# Zigbee.net
KiCad netlist of a schematic drawn in Altium Designer
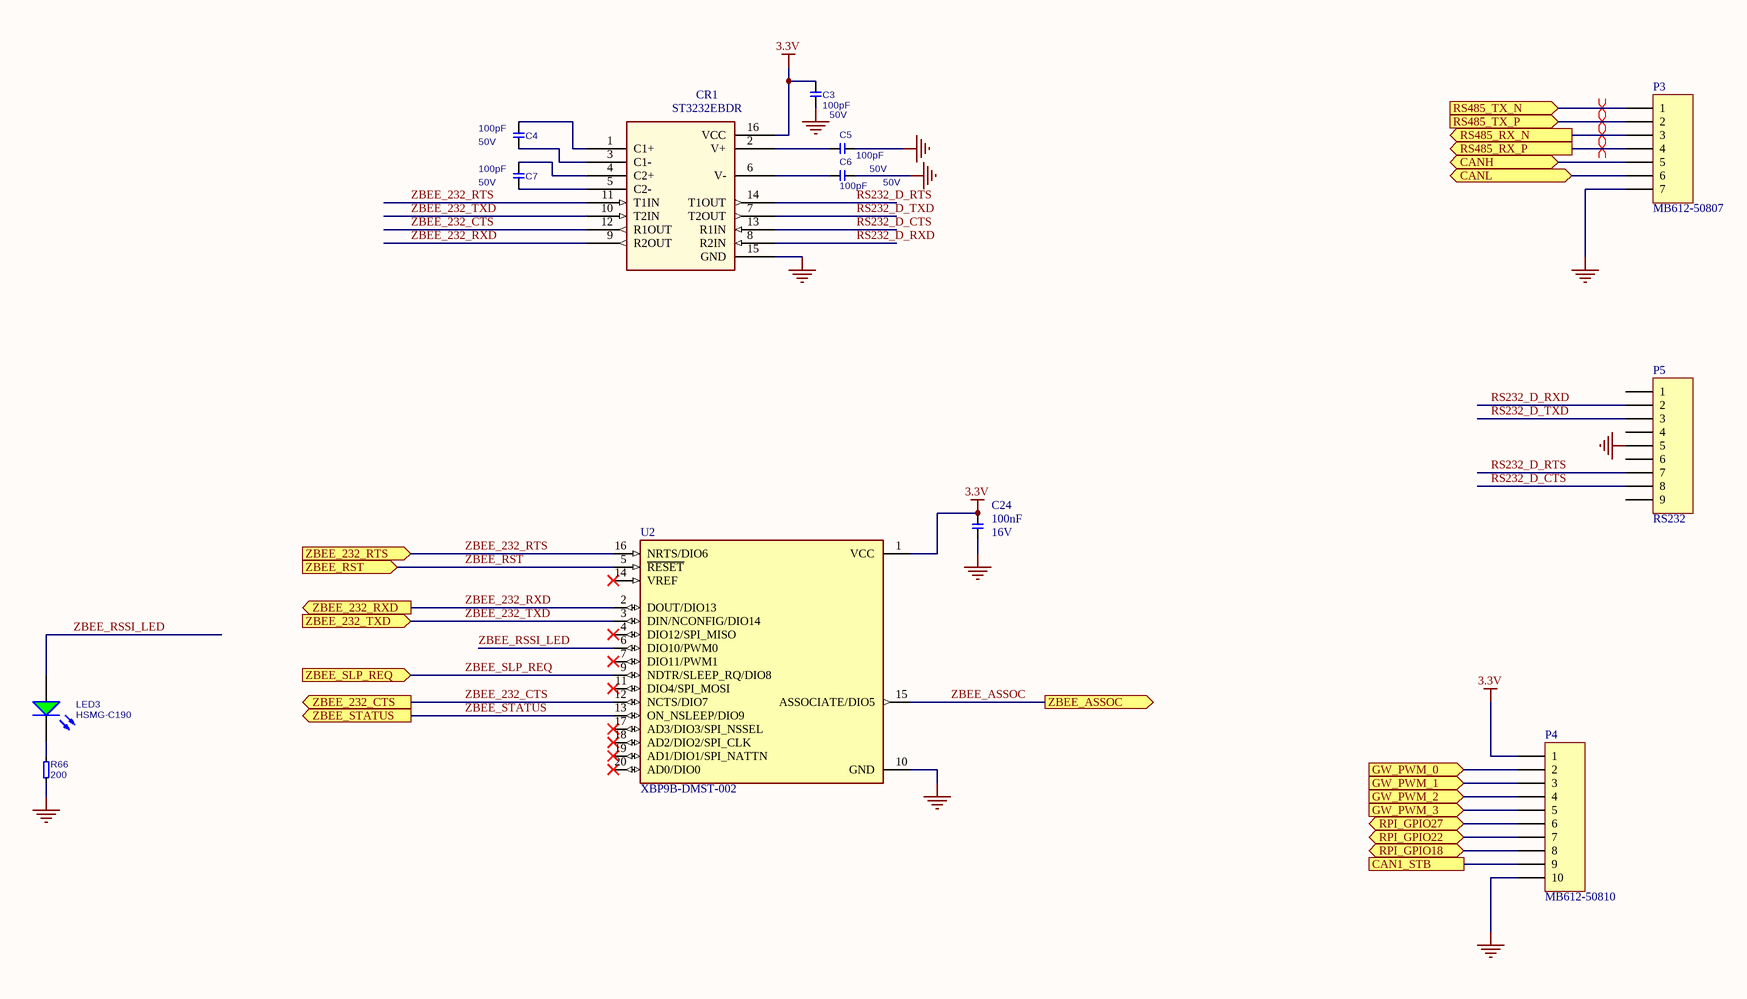
[diagram p0: Zigbee.SchDoc]

(export (version "E")
  (design (tool "Eeschema 10.0.6"))
  (components
    (comp (ref "C3")
      (value "100pF")
      (footprint "CAPC1005X60N")
      (description "Capacitor Ceramic X7R 100pF 50V 10% 0402")
      (fields (field (name "TOLERANCE") "10%") (field (name "RATING") "50V"))
      (libsource (lib "Iris") (part "C-X7R-100pF-50V-10%-0402"))
    )
    (comp (ref "C4")
      (value "100pF")
      (footprint "CAPC1005X60N")
      (description "Capacitor Ceramic X7R 100pF 50V 10% 0402")
      (fields (field (name "TOLERANCE") "10%") (field (name "RATING") "50V"))
      (libsource (lib "Iris") (part "C-X7R-100pF-50V-10%-0402"))
    )
    (comp (ref "C5")
      (value "100pF")
      (footprint "CAPC1005X60N")
      (description "Capacitor Ceramic X7R 100pF 50V 10% 0402")
      (fields (field (name "TOLERANCE") "10%") (field (name "RATING") "50V"))
      (libsource (lib "Iris") (part "C-X7R-100pF-50V-10%-0402"))
    )
    (comp (ref "C6")
      (value "100pF")
      (footprint "CAPC1005X60N")
      (description "Capacitor Ceramic X7R 100pF 50V 10% 0402")
      (fields (field (name "TOLERANCE") "10%") (field (name "RATING") "50V"))
      (libsource (lib "Iris") (part "C-X7R-100pF-50V-10%-0402"))
    )
    (comp (ref "C7")
      (value "100pF")
      (footprint "CAPC1005X60N")
      (description "Capacitor Ceramic X7R 100pF 50V 10% 0402")
      (fields (field (name "TOLERANCE") "10%") (field (name "RATING") "50V"))
      (libsource (lib "Iris") (part "C-X7R-100pF-50V-10%-0402"))
    )
    (comp (ref "C24")
      (value "100nF")
      (footprint "T_CAPC0603X33N")
      (description "Capacitor Ceramic X7R 100nF 16V 10% 0603")
      (fields (field (name "TOLERANCE") "10%") (field (name "RATING") "16V"))
      (libsource (lib "Iris") (part "C-X7R-100nF-16V-10%-0603"))
    )
    (comp (ref "CR1")
      (value "ST3232EBDR")
      (footprint "SO-16_STM")
      (libsource (lib "Schlib1") (part "ST3232EBDR"))
    )
    (comp (ref "LED3")
      (value "LED")
      (footprint "LEDC1608X80N")
      (description "Surface mount LED green 20mA")
      (fields (field (name "MANUFACTURER PART NO.") "HSMG-C190"))
      (libsource (lib "Iris") (part "LED-Avago-HSMG-C190"))
    )
    (comp (ref "P3")
      (value "MB612-50807")
      (footprint "MB612-50807")
      (description "Header, 7-Pin")
      (fields (field (name "PUBLISHER") "Altium Limited"))
      (libsource (lib "Miscellaneous Connectors") (part "Header 7"))
    )
    (comp (ref "P4")
      (value "MB612-50810")
      (footprint "1729186 5.08 - 10pos")
      (description "Header, 10-Pin")
      (fields (field (name "PUBLISHER") "Altium Limited"))
      (libsource (lib "Miscellaneous Connectors") (part "Header 10"))
    )
    (comp (ref "P5")
      (value "RS232")
      (footprint "2301843-1")
      (description "2301843-1")
      (fields (field (name "PUBLISHER") "Altium Limited"))
      (libsource (lib "Miscellaneous Connectors") (part "Header 9"))
    )
    (comp (ref "R66")
      (value "200")
      (footprint "RESC1005X40N")
      (description "Resistor 1 Kohm 63mW 5% 0402")
      (fields (field (name "TOLERANCE") "5%"))
      (libsource (lib "Iris") (part "R-1KR-63mW-5%-0402"))
    )
    (comp (ref "U2")
      (value "XBP9B-DMST-002")
      (footprint "DIP2200W51P200L3294H279Q20P")
      (description "General ISM < 1GHz Transceiver Module 900MHz Antenna Not Included, RP-SMA Through Hole")
      (fields (field (name "MF") "Digi International"))
      (libsource (lib "Schlib1") (part "XBP9B-DMST-002"))
    )
  )
  (nets
    (net (code "1") (name "/CAN1_STB") (class "Default")
      (node (ref "P4") (pin "9") (pinfunction "9_9") (pintype "passive"))
    )
    (net (code "2") (name "/CANH") (class "Default")
      (node (ref "P3") (pin "5") (pinfunction "5_5") (pintype "passive"))
    )
    (net (code "3") (name "/CANL") (class "Default")
      (node (ref "P3") (pin "6") (pinfunction "6_6") (pintype "passive"))
    )
    (net (code "4") (name "/GW_PWM_0") (class "Default")
      (node (ref "P4") (pin "2") (pinfunction "2_2") (pintype "passive"))
    )
    (net (code "5") (name "/GW_PWM_1") (class "Default")
      (node (ref "P4") (pin "3") (pinfunction "3_3") (pintype "passive"))
    )
    (net (code "6") (name "/GW_PWM_2") (class "Default")
      (node (ref "P4") (pin "4") (pinfunction "4_4") (pintype "passive"))
    )
    (net (code "7") (name "/GW_PWM_3") (class "Default")
      (node (ref "P4") (pin "5") (pinfunction "5_5") (pintype "passive"))
    )
    (net (code "8") (name "/RPI_GPIO18") (class "Default")
      (node (ref "P4") (pin "8") (pinfunction "8_8") (pintype "passive"))
    )
    (net (code "9") (name "/RPI_GPIO22") (class "Default")
      (node (ref "P4") (pin "7") (pinfunction "7_7") (pintype "passive"))
    )
    (net (code "10") (name "/RPI_GPIO27") (class "Default")
      (node (ref "P4") (pin "6") (pinfunction "6_6") (pintype "passive"))
    )
    (net (code "11") (name "/RS232_D_CTS") (class "Default")
      (node (ref "CR1") (pin "13") (pinfunction "R1IN_13") (pintype "input"))
      (node (ref "P5") (pin "8") (pinfunction "8_8") (pintype "passive"))
    )
    (net (code "12") (name "/RS232_D_RTS") (class "Default")
      (node (ref "CR1") (pin "14") (pinfunction "T1OUT_14") (pintype "output"))
      (node (ref "P5") (pin "7") (pinfunction "7_7") (pintype "passive"))
    )
    (net (code "13") (name "/RS232_D_RXD") (class "Default")
      (node (ref "CR1") (pin "8") (pinfunction "R2IN_8") (pintype "input"))
      (node (ref "P5") (pin "2") (pinfunction "2_2") (pintype "passive"))
    )
    (net (code "14") (name "/RS232_D_TXD") (class "Default")
      (node (ref "CR1") (pin "7") (pinfunction "T2OUT_7") (pintype "output"))
      (node (ref "P5") (pin "3") (pinfunction "3_3") (pintype "passive"))
    )
    (net (code "15") (name "/RS485_RX_N") (class "Default")
      (node (ref "P3") (pin "3") (pinfunction "3_3") (pintype "passive"))
    )
    (net (code "16") (name "/RS485_RX_P") (class "Default")
      (node (ref "P3") (pin "4") (pinfunction "4_4") (pintype "passive"))
    )
    (net (code "17") (name "/RS485_TX_N") (class "Default")
      (node (ref "P3") (pin "1") (pinfunction "1_1") (pintype "passive"))
    )
    (net (code "18") (name "/RS485_TX_P") (class "Default")
      (node (ref "P3") (pin "2") (pinfunction "2_2") (pintype "passive"))
    )
    (net (code "19") (name "/ZBEE_232_CTS") (class "Default")
      (node (ref "CR1") (pin "12") (pinfunction "R1OUT_12") (pintype "output"))
      (node (ref "U2") (pin "12") (pinfunction "NCTS/DIO7_12") (pintype "bidirectional"))
    )
    (net (code "20") (name "/ZBEE_232_RTS") (class "Default")
      (node (ref "CR1") (pin "11") (pinfunction "T1IN_11") (pintype "input"))
      (node (ref "U2") (pin "16") (pinfunction "NRTS/DIO6_16") (pintype "input"))
    )
    (net (code "21") (name "/ZBEE_232_RXD") (class "Default")
      (node (ref "CR1") (pin "9") (pinfunction "R2OUT_9") (pintype "output"))
      (node (ref "U2") (pin "2") (pinfunction "DOUT/DIO13_2") (pintype "bidirectional"))
    )
    (net (code "22") (name "/ZBEE_232_TXD") (class "Default")
      (node (ref "CR1") (pin "10") (pinfunction "T2IN_10") (pintype "input"))
      (node (ref "U2") (pin "3") (pinfunction "DIN/NCONFIG/DIO14_3") (pintype "bidirectional"))
    )
    (net (code "23") (name "/ZBEE_ASSOC") (class "Default")
      (node (ref "U2") (pin "15") (pinfunction "ASSOCIATE/DIO5_15") (pintype "output"))
    )
    (net (code "24") (name "/ZBEE_RSSI_LED") (class "Default")
      (node (ref "LED3") (pin "2") (pinfunction "A_2") (pintype "passive"))
      (node (ref "U2") (pin "6") (pinfunction "DIO10/PWM0_6") (pintype "bidirectional"))
    )
    (net (code "25") (name "/ZBEE_RST") (class "Default")
      (node (ref "U2") (pin "5") (pinfunction "~{RESET}_5") (pintype "input"))
    )
    (net (code "26") (name "/ZBEE_SLP_REQ") (class "Default")
      (node (ref "U2") (pin "9") (pinfunction "NDTR/SLEEP_RQ/DIO8_9") (pintype "bidirectional"))
    )
    (net (code "27") (name "/ZBEE_STATUS") (class "Default")
      (node (ref "U2") (pin "13") (pinfunction "ON_NSLEEP/DIO9_13") (pintype "bidirectional"))
    )
    (net (code "28") (name "3.3V") (class "Default")
      (node (ref "C24") (pin "2") (pinfunction "2_2") (pintype "passive"))
      (node (ref "C3") (pin "1") (pinfunction "1_1") (pintype "passive"))
      (node (ref "CR1") (pin "16") (pinfunction "VCC_16") (pintype "power_in"))
      (node (ref "P4") (pin "1") (pinfunction "1_1") (pintype "passive"))
      (node (ref "U2") (pin "1") (pinfunction "VCC_1") (pintype "power_in"))
    )
    (net (code "29") (name "GND") (class "Default")
      (node (ref "C24") (pin "1") (pinfunction "1_1") (pintype "passive"))
      (node (ref "C3") (pin "2") (pinfunction "2_2") (pintype "passive"))
      (node (ref "C5") (pin "1") (pinfunction "1_1") (pintype "passive"))
      (node (ref "C6") (pin "1") (pinfunction "1_1") (pintype "passive"))
      (node (ref "CR1") (pin "15") (pinfunction "GND_15") (pintype "power_in"))
      (node (ref "P3") (pin "7") (pinfunction "7_7") (pintype "passive"))
      (node (ref "P4") (pin "10") (pinfunction "10_10") (pintype "passive"))
      (node (ref "P5") (pin "5") (pinfunction "5_5") (pintype "passive"))
      (node (ref "R66") (pin "2") (pinfunction "2_2") (pintype "passive"))
      (node (ref "U2") (pin "10") (pinfunction "GND_10") (pintype "power_in"))
    )
    (net (code "30") (name "Net-(CR1-C1+)") (class "Default")
      (node (ref "C4") (pin "2") (pinfunction "2_2") (pintype "passive"))
      (node (ref "CR1") (pin "1") (pinfunction "C1+_1") (pintype "passive"))
    )
    (net (code "31") (name "Net-(CR1-C1-)") (class "Default")
      (node (ref "C4") (pin "1") (pinfunction "1_1") (pintype "passive"))
      (node (ref "CR1") (pin "3") (pinfunction "C1-_3") (pintype "passive"))
    )
    (net (code "32") (name "Net-(CR1-C2+)") (class "Default")
      (node (ref "C7") (pin "2") (pinfunction "2_2") (pintype "passive"))
      (node (ref "CR1") (pin "4") (pinfunction "C2+_4") (pintype "passive"))
    )
    (net (code "33") (name "Net-(CR1-C2-)") (class "Default")
      (node (ref "C7") (pin "1") (pinfunction "1_1") (pintype "passive"))
      (node (ref "CR1") (pin "5") (pinfunction "C2-_5") (pintype "passive"))
    )
    (net (code "34") (name "Net-(CR1-V+)") (class "Default")
      (node (ref "C5") (pin "2") (pinfunction "2_2") (pintype "passive"))
      (node (ref "CR1") (pin "2") (pinfunction "V+_2") (pintype "power_in"))
    )
    (net (code "35") (name "Net-(CR1-V-)") (class "Default")
      (node (ref "C6") (pin "2") (pinfunction "2_2") (pintype "passive"))
      (node (ref "CR1") (pin "6") (pinfunction "V-_6") (pintype "power_in"))
    )
    (net (code "36") (name "Net-(LED3-K)") (class "Default")
      (node (ref "LED3") (pin "1") (pinfunction "K_1") (pintype "passive"))
      (node (ref "R66") (pin "1") (pinfunction "1_1") (pintype "passive"))
    )
    (net (code "37") (name "unconnected-(P5-Pad1)") (class "Default")
      (node (ref "P5") (pin "1") (pinfunction "1_1") (pintype "passive"))
    )
    (net (code "38") (name "unconnected-(P5-Pad4)") (class "Default")
      (node (ref "P5") (pin "4") (pinfunction "4_4") (pintype "passive"))
    )
    (net (code "39") (name "unconnected-(P5-Pad6)") (class "Default")
      (node (ref "P5") (pin "6") (pinfunction "6_6") (pintype "passive"))
    )
    (net (code "40") (name "unconnected-(P5-Pad9)") (class "Default")
      (node (ref "P5") (pin "9") (pinfunction "9_9") (pintype "passive"))
    )
    (net (code "41") (name "unconnected-(U2-AD0{slash}DIO0-Pad20)") (class "Default")
      (node (ref "U2") (pin "20") (pinfunction "AD0/DIO0_20") (pintype "bidirectional+no_connect"))
    )
    (net (code "42") (name "unconnected-(U2-AD1{slash}DIO1{slash}SPI_NATTN-Pad19)") (class "Default")
      (node (ref "U2") (pin "19") (pinfunction "AD1/DIO1/SPI_NATTN_19") (pintype "bidirectional+no_connect"))
    )
    (net (code "43") (name "unconnected-(U2-AD2{slash}DIO2{slash}SPI_CLK-Pad18)") (class "Default")
      (node (ref "U2") (pin "18") (pinfunction "AD2/DIO2/SPI_CLK_18") (pintype "bidirectional+no_connect"))
    )
    (net (code "44") (name "unconnected-(U2-AD3{slash}DIO3{slash}SPI_NSSEL-Pad17)") (class "Default")
      (node (ref "U2") (pin "17") (pinfunction "AD3/DIO3/SPI_NSSEL_17") (pintype "bidirectional+no_connect"))
    )
    (net (code "45") (name "unconnected-(U2-DIO4{slash}SPI_MOSI-Pad11)") (class "Default")
      (node (ref "U2") (pin "11") (pinfunction "DIO4/SPI_MOSI_11") (pintype "bidirectional+no_connect"))
    )
    (net (code "46") (name "unconnected-(U2-DIO11{slash}PWM1-Pad7)") (class "Default")
      (node (ref "U2") (pin "7") (pinfunction "DIO11/PWM1_7") (pintype "bidirectional+no_connect"))
    )
    (net (code "47") (name "unconnected-(U2-DIO12{slash}SPI_MISO-Pad4)") (class "Default")
      (node (ref "U2") (pin "4") (pinfunction "DIO12/SPI_MISO_4") (pintype "bidirectional+no_connect"))
    )
    (net (code "48") (name "unconnected-(U2-VREF-Pad14)") (class "Default")
      (node (ref "U2") (pin "14") (pinfunction "VREF_14") (pintype "input+no_connect"))
    )
  )
)
